# OpenTag3_Sensors.net
KiCad netlist of a schematic drawn in Altium Designer
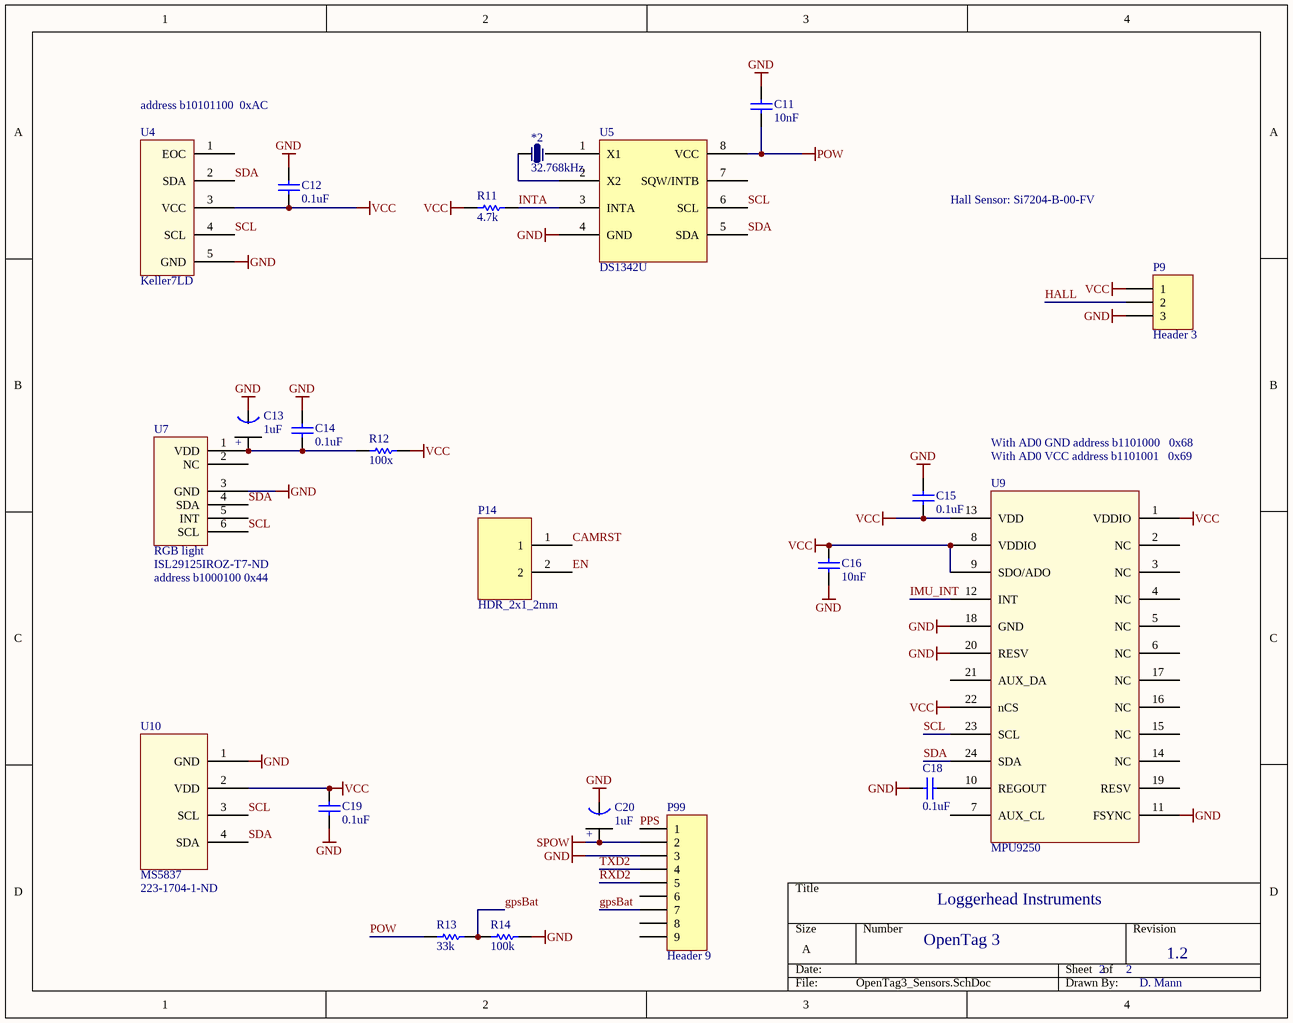
[diagram p0: OpenTag3_Sensors.SchDoc]

(export (version "E")
  (design (tool "Eeschema 10.0.6"))
  (components
    (comp (ref "*2")
      (value "32.768kHz")
      (footprint "XTAL-ABS06")
      (libsource (lib "Loggerhead") (part "XTAL_ABS06"))
    )
    (comp (ref "C11")
      (value "10nF")
      (footprint "0402")
      (description "Ceramic Chip Capacitor - Standard")
      (fields (field (name "PUBLISHER") "Altium Limited"))
      (libsource (lib "KEMET Chip Capacitor") (part "C0402"))
    )
    (comp (ref "C12")
      (value "0.1uF")
      (footprint "0402")
      (description "Ceramic Chip Capacitor - Standard")
      (fields (field (name "PUBLISHER") "Altium Limited"))
      (libsource (lib "KEMET Chip Capacitor") (part "C0402"))
    )
    (comp (ref "C13") (value "1uF") (footprint "Tant0805") (libsource (lib "Loggerhead") (part "Tant0805")))
    (comp (ref "C14")
      (value "0.1uF")
      (footprint "0402")
      (description "Ceramic Chip Capacitor - Standard")
      (fields (field (name "PUBLISHER") "Altium Limited"))
      (libsource (lib "KEMET Chip Capacitor") (part "C0402"))
    )
    (comp (ref "C15")
      (value "0.1uF")
      (footprint "0402")
      (description "Ceramic Chip Capacitor - Standard")
      (fields (field (name "PUBLISHER") "Altium Limited"))
      (libsource (lib "KEMET Chip Capacitor") (part "C0402"))
    )
    (comp (ref "C16")
      (value "10nF")
      (footprint "0402")
      (description "Ceramic Chip Capacitor - Standard")
      (fields (field (name "PUBLISHER") "Altium Limited"))
      (libsource (lib "KEMET Chip Capacitor") (part "C0402"))
    )
    (comp (ref "C18")
      (value "0.1uF")
      (footprint "0402")
      (description "Ceramic Chip Capacitor - Standard")
      (fields (field (name "PUBLISHER") "Altium Limited"))
      (libsource (lib "KEMET Chip Capacitor") (part "C0402"))
    )
    (comp (ref "C19")
      (value "0.1uF")
      (footprint "0402")
      (description "Ceramic Chip Capacitor - Standard")
      (fields (field (name "PUBLISHER") "Altium Limited"))
      (libsource (lib "KEMET Chip Capacitor") (part "C0402"))
    )
    (comp (ref "C20") (value "1uF") (footprint "Tant0805") (libsource (lib "Loggerhead") (part "Tant0805")))
    (comp (ref "P9")
      (value "Header 3")
      (footprint "HDR1X3")
      (description "Header, 3-Pin")
      (fields (field (name "PUBLISHER") "Altium Limited"))
      (libsource (lib "Miscellaneous Connectors") (part "Header 3"))
    )
    (comp (ref "P14")
      (value "HDR_2x1_2mm")
      (footprint "HDR_2x1_2mm")
      (libsource (lib "Loggerhead") (part "HDR_2x1_2mm"))
    )
    (comp (ref "P99")
      (value "Header 9")
      (footprint "HDR1X9")
      (description "Header, 9-Pin")
      (fields (field (name "PUBLISHER") "Altium Limited"))
      (libsource (lib "Miscellaneous Connectors") (part "Header 9"))
    )
    (comp (ref "R11")
      (value "4.7k")
      (footprint "3-0603")
      (fields (field (name "PUBLISHER") "Altium Limited"))
      (libsource (lib "Panasonic Resistor") (part "ERJ3RK"))
    )
    (comp (ref "R12")
      (value "100x")
      (footprint "3-0603")
      (fields (field (name "PUBLISHER") "Altium Limited"))
      (libsource (lib "Panasonic Resistor") (part "ERJ3RK"))
    )
    (comp (ref "R13")
      (value "33k")
      (footprint "3-0603")
      (fields (field (name "PUBLISHER") "Altium Limited"))
      (libsource (lib "Panasonic Resistor") (part "ERJ3RK"))
    )
    (comp (ref "R14")
      (value "100k")
      (footprint "3-0603")
      (fields (field (name "PUBLISHER") "Altium Limited"))
      (libsource (lib "Panasonic Resistor") (part "ERJ3RK"))
    )
    (comp (ref "U4")
      (value "Keller7LD")
      (footprint "Keller7LD")
      (description "Keller Pressure/Temp")
      (libsource (lib "Loggerhead") (part "Keller 7LD"))
    )
    (comp (ref "U5") (value "DS1342U") (footprint "uSOP8") (libsource (lib "Loggerhead") (part "DS1337")))
    (comp (ref "U7")
      (value "RGB light")
      (footprint "ODFN")
      (description "RGB light sensor")
      (fields (field (name "SUPPLIER PART NUMBER 1") "ISL29125IROZ-T7-ND"))
      (libsource (lib "Loggerhead") (part "ISL29125"))
    )
    (comp (ref "U9")
      (value "MPU9250")
      (footprint "MPU6500")
      (description "Invensense")
      (libsource (lib "Loggerhead") (part "MPU-9250"))
    )
    (comp (ref "U10")
      (value "MS5837")
      (footprint "MS5837")
      (description "Pressure/Temp")
      (fields (field (name "SUPPLIER PART NUMBER 1") "223-1704-1-ND"))
      (libsource (lib "Loggerhead") (part "MS5837"))
    )
  )
  (nets
    (net (code "1") (name "/CAMRST") (class "Default")
      (node (ref "P14") (pin "1") (pinfunction "1_1") (pintype "passive"))
    )
    (net (code "2") (name "/EN") (class "Default")
      (node (ref "P14") (pin "2") (pinfunction "2_2") (pintype "passive"))
    )
    (net (code "3") (name "/HALL") (class "Default")
      (node (ref "P9") (pin "2") (pinfunction "2_2") (pintype "passive"))
    )
    (net (code "4") (name "/IMU_INT") (class "Default")
      (node (ref "U9") (pin "12") (pinfunction "INT_12") (pintype "passive"))
    )
    (net (code "5") (name "/INTA") (class "Default")
      (node (ref "R11") (pin "2") (pinfunction "2_2") (pintype "passive"))
      (node (ref "U5") (pin "3") (pinfunction "INTA_3") (pintype "passive"))
    )
    (net (code "6") (name "/PPS") (class "Default")
      (node (ref "P99") (pin "1") (pinfunction "1_1") (pintype "passive"))
    )
    (net (code "7") (name "/RXD2") (class "Default")
      (node (ref "P99") (pin "5") (pinfunction "5_5") (pintype "passive"))
    )
    (net (code "8") (name "/SCL") (class "Default")
      (node (ref "U10") (pin "3") (pinfunction "SCL_3") (pintype "passive"))
      (node (ref "U4") (pin "4") (pinfunction "SCL_4") (pintype "passive"))
      (node (ref "U5") (pin "6") (pinfunction "SCL_6") (pintype "passive"))
      (node (ref "U7") (pin "6") (pinfunction "SCL_6") (pintype "passive"))
      (node (ref "U9") (pin "23") (pinfunction "SCL_23") (pintype "passive"))
    )
    (net (code "9") (name "/SDA") (class "Default")
      (node (ref "U10") (pin "4") (pinfunction "SDA_4") (pintype "passive"))
      (node (ref "U4") (pin "2") (pinfunction "SDA_2") (pintype "passive"))
      (node (ref "U5") (pin "5") (pinfunction "SDA_5") (pintype "passive"))
      (node (ref "U7") (pin "4") (pinfunction "SDA_4") (pintype "passive"))
      (node (ref "U9") (pin "24") (pinfunction "SDA_24") (pintype "passive"))
    )
    (net (code "10") (name "/TXD2") (class "Default")
      (node (ref "P99") (pin "4") (pinfunction "4_4") (pintype "passive"))
    )
    (net (code "11") (name "/gpsBat") (class "Default")
      (node (ref "P99") (pin "7") (pinfunction "7_7") (pintype "passive"))
      (node (ref "R13") (pin "1") (pinfunction "1_1") (pintype "passive"))
      (node (ref "R14") (pin "2") (pinfunction "2_2") (pintype "passive"))
    )
    (net (code "12") (name "GND") (class "Default")
      (node (ref "C11") (pin "1") (pinfunction "1_1") (pintype "passive"))
      (node (ref "C12") (pin "2") (pinfunction "2_2") (pintype "passive"))
      (node (ref "C13") (pin "1") (pinfunction "GND_1") (pintype "passive"))
      (node (ref "C14") (pin "2") (pinfunction "2_2") (pintype "passive"))
      (node (ref "C15") (pin "2") (pinfunction "2_2") (pintype "passive"))
      (node (ref "C16") (pin "2") (pinfunction "2_2") (pintype "passive"))
      (node (ref "C18") (pin "1") (pinfunction "1_1") (pintype "passive"))
      (node (ref "C19") (pin "1") (pinfunction "1_1") (pintype "passive"))
      (node (ref "C20") (pin "1") (pinfunction "GND_1") (pintype "passive"))
      (node (ref "P9") (pin "3") (pinfunction "3_3") (pintype "passive"))
      (node (ref "P99") (pin "3") (pinfunction "3_3") (pintype "passive"))
      (node (ref "R14") (pin "1") (pinfunction "1_1") (pintype "passive"))
      (node (ref "U10") (pin "1") (pinfunction "GND_1") (pintype "passive"))
      (node (ref "U4") (pin "5") (pinfunction "GND_5") (pintype "passive"))
      (node (ref "U5") (pin "4") (pinfunction "GND_4") (pintype "passive"))
      (node (ref "U7") (pin "3") (pinfunction "GND_3") (pintype "passive"))
      (node (ref "U9") (pin "11") (pinfunction "FSYNC_11") (pintype "passive"))
      (node (ref "U9") (pin "18") (pinfunction "GND_18") (pintype "passive"))
      (node (ref "U9") (pin "20") (pinfunction "RESV_20") (pintype "passive"))
    )
    (net (code "13") (name "Net-(C13-+)") (class "Default")
      (node (ref "C13") (pin "2") (pinfunction "+_2") (pintype "passive"))
      (node (ref "C14") (pin "1") (pinfunction "1_1") (pintype "passive"))
      (node (ref "R12") (pin "2") (pinfunction "2_2") (pintype "passive"))
      (node (ref "U7") (pin "1") (pinfunction "VDD_1") (pintype "passive"))
    )
    (net (code "14") (name "Net-(U5-X1)") (class "Default")
      (node (ref "*2") (pin "2") (pinfunction "2_2") (pintype "passive"))
      (node (ref "U5") (pin "1") (pinfunction "X1_1") (pintype "passive"))
    )
    (net (code "15") (name "Net-(U5-X2)") (class "Default")
      (node (ref "*2") (pin "1") (pinfunction "1_1") (pintype "passive"))
      (node (ref "U5") (pin "2") (pinfunction "X2_2") (pintype "passive"))
    )
    (net (code "16") (name "Net-(U9-REGOUT)") (class "Default")
      (node (ref "C18") (pin "2") (pinfunction "2_2") (pintype "passive"))
      (node (ref "U9") (pin "10") (pinfunction "REGOUT_10") (pintype "passive"))
    )
    (net (code "17") (name "POW") (class "Default")
      (node (ref "C11") (pin "2") (pinfunction "2_2") (pintype "passive"))
      (node (ref "R13") (pin "2") (pinfunction "2_2") (pintype "passive"))
      (node (ref "U5") (pin "8") (pinfunction "VCC_8") (pintype "power_in"))
    )
    (net (code "18") (name "SPOW") (class "Default")
      (node (ref "C20") (pin "2") (pinfunction "+_2") (pintype "passive"))
      (node (ref "P99") (pin "2") (pinfunction "2_2") (pintype "passive"))
    )
    (net (code "19") (name "VCC") (class "Default")
      (node (ref "C12") (pin "1") (pinfunction "1_1") (pintype "passive"))
      (node (ref "C15") (pin "1") (pinfunction "1_1") (pintype "passive"))
      (node (ref "C16") (pin "1") (pinfunction "1_1") (pintype "passive"))
      (node (ref "C19") (pin "2") (pinfunction "2_2") (pintype "passive"))
      (node (ref "P9") (pin "1") (pinfunction "1_1") (pintype "passive"))
      (node (ref "R11") (pin "1") (pinfunction "1_1") (pintype "passive"))
      (node (ref "R12") (pin "1") (pinfunction "1_1") (pintype "passive"))
      (node (ref "U10") (pin "2") (pinfunction "VDD_2") (pintype "passive"))
      (node (ref "U4") (pin "3") (pinfunction "VCC_3") (pintype "passive"))
      (node (ref "U9") (pin "1") (pinfunction "VDDIO_1") (pintype "passive"))
      (node (ref "U9") (pin "13") (pinfunction "VDD_13") (pintype "passive"))
      (node (ref "U9") (pin "22") (pinfunction "nCS_22") (pintype "passive"))
      (node (ref "U9") (pin "8") (pinfunction "VDDIO_8") (pintype "passive"))
      (node (ref "U9") (pin "9") (pinfunction "SDO/ADO_9") (pintype "passive"))
    )
    (net (code "20") (name "unconnected-(P99-Pad6)") (class "Default")
      (node (ref "P99") (pin "6") (pinfunction "6_6") (pintype "passive"))
    )
    (net (code "21") (name "unconnected-(P99-Pad8)") (class "Default")
      (node (ref "P99") (pin "8") (pinfunction "8_8") (pintype "passive"))
    )
    (net (code "22") (name "unconnected-(P99-Pad9)") (class "Default")
      (node (ref "P99") (pin "9") (pinfunction "9_9") (pintype "passive"))
    )
    (net (code "23") (name "unconnected-(U4-EOC-Pad1)") (class "Default")
      (node (ref "U4") (pin "1") (pinfunction "EOC_1") (pintype "passive"))
    )
    (net (code "24") (name "unconnected-(U5-SQW{slash}INTB-Pad7)") (class "Default")
      (node (ref "U5") (pin "7") (pinfunction "SQW/INTB_7") (pintype "passive"))
    )
    (net (code "25") (name "unconnected-(U7-INT-Pad5)") (class "Default")
      (node (ref "U7") (pin "5") (pinfunction "INT_5") (pintype "passive"))
    )
    (net (code "26") (name "unconnected-(U7-NC-Pad2)") (class "Default")
      (node (ref "U7") (pin "2") (pinfunction "NC_2") (pintype "passive"))
    )
    (net (code "27") (name "unconnected-(U9-AUX_CL-Pad7)") (class "Default")
      (node (ref "U9") (pin "7") (pinfunction "AUX_CL_7") (pintype "passive"))
    )
    (net (code "28") (name "unconnected-(U9-AUX_DA-Pad21)") (class "Default")
      (node (ref "U9") (pin "21") (pinfunction "AUX_DA_21") (pintype "passive"))
    )
    (net (code "29") (name "unconnected-(U9-NC-Pad2)") (class "Default")
      (node (ref "U9") (pin "2") (pinfunction "NC_2") (pintype "passive"))
    )
    (net (code "30") (name "unconnected-(U9-NC-Pad3)") (class "Default")
      (node (ref "U9") (pin "3") (pinfunction "NC_3") (pintype "passive"))
    )
    (net (code "31") (name "unconnected-(U9-NC-Pad4)") (class "Default")
      (node (ref "U9") (pin "4") (pinfunction "NC_4") (pintype "passive"))
    )
    (net (code "32") (name "unconnected-(U9-NC-Pad5)") (class "Default")
      (node (ref "U9") (pin "5") (pinfunction "NC_5") (pintype "passive"))
    )
    (net (code "33") (name "unconnected-(U9-NC-Pad6)") (class "Default")
      (node (ref "U9") (pin "6") (pinfunction "NC_6") (pintype "passive"))
    )
    (net (code "34") (name "unconnected-(U9-NC-Pad14)") (class "Default")
      (node (ref "U9") (pin "14") (pinfunction "NC_14") (pintype "passive"))
    )
    (net (code "35") (name "unconnected-(U9-NC-Pad15)") (class "Default")
      (node (ref "U9") (pin "15") (pinfunction "NC_15") (pintype "passive"))
    )
    (net (code "36") (name "unconnected-(U9-NC-Pad16)") (class "Default")
      (node (ref "U9") (pin "16") (pinfunction "NC_16") (pintype "passive"))
    )
    (net (code "37") (name "unconnected-(U9-NC-Pad17)") (class "Default")
      (node (ref "U9") (pin "17") (pinfunction "NC_17") (pintype "passive"))
    )
    (net (code "38") (name "unconnected-(U9-RESV-Pad19)") (class "Default")
      (node (ref "U9") (pin "19") (pinfunction "RESV_19") (pintype "passive"))
    )
  )
)
